# DobbelSteen_with_programing_header.net
KiCad netlist of a schematic drawn in EAGLE
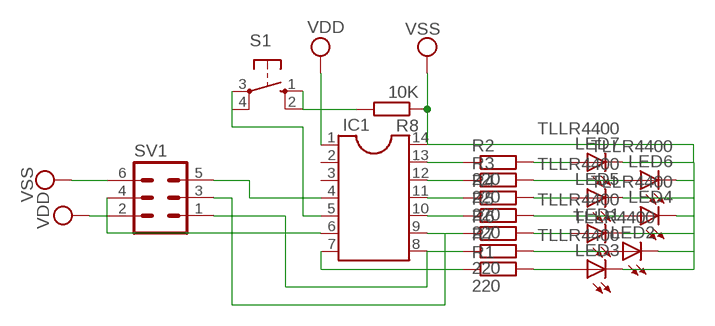
[diagram p0: schematic, sheet 1]

(export (version "E")
  (design (tool "Eeschema 10.0.6"))
  (components
    (comp (ref "IC1")
      (value "DIL14S")
      (footprint "eagle-import:SOCKET-14")
      (libsource (lib "eagle-import") (part "DIL14S"))
    )
    (comp (ref "LED1")
      (value "TLLR4400")
      (footprint "eagle-import:LED3MM")
      (fields (field (name "MF") "VISHAY SEMICONDUCTOR"))
      (libsource (lib "eagle-import") (part "TLLR4400"))
    )
    (comp (ref "LED2")
      (value "TLLR4400")
      (footprint "eagle-import:LED3MM")
      (fields (field (name "MF") "VISHAY SEMICONDUCTOR"))
      (libsource (lib "eagle-import") (part "TLLR4400"))
    )
    (comp (ref "LED3")
      (value "TLLR4400")
      (footprint "eagle-import:LED3MM")
      (fields (field (name "MF") "VISHAY SEMICONDUCTOR"))
      (libsource (lib "eagle-import") (part "TLLR4400"))
    )
    (comp (ref "LED4")
      (value "TLLR4400")
      (footprint "eagle-import:LED3MM")
      (fields (field (name "MF") "VISHAY SEMICONDUCTOR"))
      (libsource (lib "eagle-import") (part "TLLR4400"))
    )
    (comp (ref "LED5")
      (value "TLLR4400")
      (footprint "eagle-import:LED3MM")
      (fields (field (name "MF") "VISHAY SEMICONDUCTOR"))
      (libsource (lib "eagle-import") (part "TLLR4400"))
    )
    (comp (ref "LED6")
      (value "TLLR4400")
      (footprint "eagle-import:LED3MM")
      (fields (field (name "MF") "VISHAY SEMICONDUCTOR"))
      (libsource (lib "eagle-import") (part "TLLR4400"))
    )
    (comp (ref "LED7")
      (value "TLLR4400")
      (footprint "eagle-import:LED3MM")
      (fields (field (name "MF") "VISHAY SEMICONDUCTOR"))
      (libsource (lib "eagle-import") (part "TLLR4400"))
    )
    (comp (ref "R1")
      (value "220")
      (footprint "eagle-import:0204_7")
      (libsource (lib "eagle-import") (part "R0204/7"))
    )
    (comp (ref "R2")
      (value "220")
      (footprint "eagle-import:0204_7")
      (libsource (lib "eagle-import") (part "R0204/7"))
    )
    (comp (ref "R3")
      (value "220")
      (footprint "eagle-import:0204_7")
      (libsource (lib "eagle-import") (part "R0204/7"))
    )
    (comp (ref "R4")
      (value "220")
      (footprint "eagle-import:0204_7")
      (libsource (lib "eagle-import") (part "R0204/7"))
    )
    (comp (ref "R5")
      (value "220")
      (footprint "eagle-import:0204_7")
      (libsource (lib "eagle-import") (part "R0204/7"))
    )
    (comp (ref "R6")
      (value "R0204/7")
      (footprint "eagle-import:0204_7")
      (libsource (lib "eagle-import") (part "R0204/7"))
    )
    (comp (ref "R7")
      (value "220")
      (footprint "eagle-import:0204_7")
      (libsource (lib "eagle-import") (part "R0204/7"))
    )
    (comp (ref "R8")
      (value "10K")
      (footprint "eagle-import:0204_7")
      (libsource (lib "eagle-import") (part "R0204/7"))
    )
    (comp (ref "S1")
      (value "10-XX")
      (footprint "eagle-import:B3F-10XX")
      (fields (field (name "MPN") "B3F-1000"))
      (libsource (lib "eagle-import") (part "10-XX"))
    )
    (comp (ref "SV1")
      (value "MA03-2")
      (footprint "eagle-import:MA03-2")
      (libsource (lib "eagle-import") (part "MA03-2"))
    )
  )
  (nets
    (net (code "1") (name "Net-(IC1-Pad4)") (class "Default")
      (node (ref "IC1") (pin "4") (pinfunction "4_4") (pintype "passive"))
      (node (ref "SV1") (pin "5") (pinfunction "5_5") (pintype "passive"))
    )
    (net (code "2") (name "Net-(IC1-Pad6)") (class "Default")
      (node (ref "IC1") (pin "6") (pinfunction "6_6") (pintype "passive"))
      (node (ref "SV1") (pin "4") (pinfunction "4_4") (pintype "passive"))
    )
    (net (code "3") (name "Net-(IC1-Pad7)") (class "Default")
      (node (ref "IC1") (pin "7") (pinfunction "7_7") (pintype "passive"))
      (node (ref "R1") (pin "1") (pinfunction "1_1") (pintype "passive"))
    )
    (net (code "4") (name "Net-(IC1-Pad8)") (class "Default")
      (node (ref "IC1") (pin "8") (pinfunction "8_8") (pintype "passive"))
      (node (ref "R7") (pin "1") (pinfunction "1_1") (pintype "passive"))
      (node (ref "SV1") (pin "1") (pinfunction "1_1") (pintype "passive"))
    )
    (net (code "5") (name "Net-(IC1-Pad9)") (class "Default")
      (node (ref "IC1") (pin "9") (pinfunction "9_9") (pintype "passive"))
      (node (ref "R6") (pin "1") (pinfunction "1_1") (pintype "passive"))
      (node (ref "SV1") (pin "3") (pinfunction "3_3") (pintype "passive"))
    )
    (net (code "6") (name "Net-(IC1-Pad10)") (class "Default")
      (node (ref "IC1") (pin "10") (pinfunction "10_10") (pintype "passive"))
      (node (ref "R5") (pin "1") (pinfunction "1_1") (pintype "passive"))
    )
    (net (code "7") (name "Net-(IC1-Pad11)") (class "Default")
      (node (ref "IC1") (pin "11") (pinfunction "11_11") (pintype "passive"))
      (node (ref "R4") (pin "1") (pinfunction "1_1") (pintype "passive"))
    )
    (net (code "8") (name "Net-(IC1-Pad12)") (class "Default")
      (node (ref "IC1") (pin "12") (pinfunction "12_12") (pintype "passive"))
      (node (ref "R3") (pin "1") (pinfunction "1_1") (pintype "passive"))
    )
    (net (code "9") (name "Net-(IC1-Pad13)") (class "Default")
      (node (ref "IC1") (pin "13") (pinfunction "13_13") (pintype "passive"))
      (node (ref "R2") (pin "1") (pinfunction "1_1") (pintype "passive"))
    )
    (net (code "10") (name "Net-(LED1-PadA)") (class "Default")
      (node (ref "LED1") (pin "A") (pinfunction "A_A") (pintype "passive"))
      (node (ref "R6") (pin "2") (pinfunction "2_2") (pintype "passive"))
    )
    (net (code "11") (name "Net-(LED2-PadA)") (class "Default")
      (node (ref "LED2") (pin "A") (pinfunction "A_A") (pintype "passive"))
      (node (ref "R7") (pin "2") (pinfunction "2_2") (pintype "passive"))
    )
    (net (code "12") (name "Net-(LED3-PadA)") (class "Default")
      (node (ref "LED3") (pin "A") (pinfunction "A_A") (pintype "passive"))
      (node (ref "R1") (pin "2") (pinfunction "2_2") (pintype "passive"))
    )
    (net (code "13") (name "Net-(LED4-PadA)") (class "Default")
      (node (ref "LED4") (pin "A") (pinfunction "A_A") (pintype "passive"))
      (node (ref "R5") (pin "2") (pinfunction "2_2") (pintype "passive"))
    )
    (net (code "14") (name "Net-(LED5-PadA)") (class "Default")
      (node (ref "LED5") (pin "A") (pinfunction "A_A") (pintype "passive"))
      (node (ref "R4") (pin "2") (pinfunction "2_2") (pintype "passive"))
    )
    (net (code "15") (name "Net-(LED6-PadA)") (class "Default")
      (node (ref "LED6") (pin "A") (pinfunction "A_A") (pintype "passive"))
      (node (ref "R3") (pin "2") (pinfunction "2_2") (pintype "passive"))
    )
    (net (code "16") (name "Net-(LED7-PadA)") (class "Default")
      (node (ref "LED7") (pin "A") (pinfunction "A_A") (pintype "passive"))
      (node (ref "R2") (pin "2") (pinfunction "2_2") (pintype "passive"))
    )
    (net (code "17") (name "Net-(S1-P)") (class "Default")
      (node (ref "IC1") (pin "5") (pinfunction "5_5") (pintype "passive"))
      (node (ref "S1") (pin "3") (pinfunction "P_3") (pintype "passive"))
      (node (ref "S1") (pin "4") (pinfunction "P1_4") (pintype "passive"))
    )
    (net (code "18") (name "Net-(S1-S)") (class "Default")
      (node (ref "R8") (pin "2") (pinfunction "2_2") (pintype "passive"))
      (node (ref "S1") (pin "1") (pinfunction "S_1") (pintype "passive"))
      (node (ref "S1") (pin "2") (pinfunction "S1_2") (pintype "passive"))
    )
    (net (code "19") (name "VDD") (class "Default")
      (node (ref "IC1") (pin "1") (pinfunction "1_1") (pintype "passive"))
      (node (ref "SV1") (pin "2") (pinfunction "2_2") (pintype "passive"))
    )
    (net (code "20") (name "VSS") (class "Default")
      (node (ref "IC1") (pin "14") (pinfunction "14_14") (pintype "passive"))
      (node (ref "LED1") (pin "K") (pinfunction "C_K") (pintype "passive"))
      (node (ref "LED2") (pin "K") (pinfunction "C_K") (pintype "passive"))
      (node (ref "LED3") (pin "K") (pinfunction "C_K") (pintype "passive"))
      (node (ref "LED4") (pin "K") (pinfunction "C_K") (pintype "passive"))
      (node (ref "LED5") (pin "K") (pinfunction "C_K") (pintype "passive"))
      (node (ref "LED6") (pin "K") (pinfunction "C_K") (pintype "passive"))
      (node (ref "LED7") (pin "K") (pinfunction "C_K") (pintype "passive"))
      (node (ref "R8") (pin "1") (pinfunction "1_1") (pintype "passive"))
      (node (ref "SV1") (pin "6") (pinfunction "6_6") (pintype "passive"))
    )
    (net (code "21") (name "unconnected-(IC1-Pad2)") (class "Default")
      (node (ref "IC1") (pin "2") (pinfunction "2_2") (pintype "passive"))
    )
    (net (code "22") (name "unconnected-(IC1-Pad3)") (class "Default")
      (node (ref "IC1") (pin "3") (pinfunction "3_3") (pintype "passive"))
    )
  )
)
